# Encoder.net
KiCad netlist of a schematic drawn in EAGLE
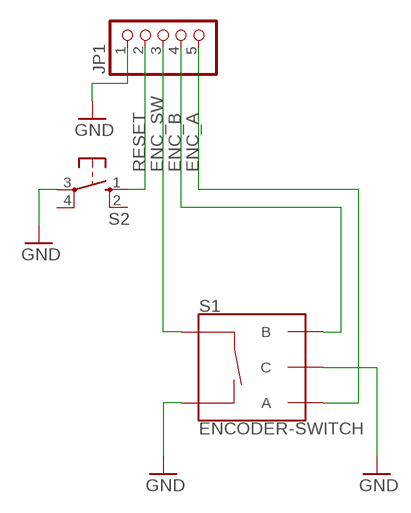
[diagram p0: schematic, sheet 1]

(export (version "E")
  (design (tool "Eeschema 10.0.6"))
  (components
    (comp (ref "JP1")
      (value "PINHD-1X5/90")
      (footprint "eagle-import:1X05_90")
      (libsource (lib "eagle-import") (part "PINHD-1X5/90"))
    )
    (comp (ref "S1")
      (value "ENCODER-SWITCH")
      (footprint "eagle-import:ROTARY_ENC_PLAIN")
      (libsource (lib "eagle-import") (part "ENCODER-SWITCH"))
    )
    (comp (ref "S2")
      (value "10-XX")
      (footprint "eagle-import:B3F-10XX")
      (fields (field (name "MPN") "B3F-1000"))
      (libsource (lib "eagle-import") (part "10-XX"))
    )
  )
  (nets
    (net (code "1") (name "/ENC_A") (class "Default")
      (node (ref "JP1") (pin "5") (pinfunction "5_5") (pintype "passive"))
      (node (ref "S1") (pin "A") (pinfunction "A_A") (pintype "bidirectional"))
    )
    (net (code "2") (name "/ENC_B") (class "Default")
      (node (ref "JP1") (pin "4") (pinfunction "4_4") (pintype "passive"))
      (node (ref "S1") (pin "B") (pinfunction "B_B") (pintype "bidirectional"))
    )
    (net (code "3") (name "/ENC_SW") (class "Default")
      (node (ref "JP1") (pin "3") (pinfunction "3_3") (pintype "passive"))
      (node (ref "S1") (pin "SW+") (pinfunction "SW+_SW+") (pintype "bidirectional"))
    )
    (net (code "4") (name "/RESET") (class "Default")
      (node (ref "JP1") (pin "2") (pinfunction "2_2") (pintype "passive"))
      (node (ref "S2") (pin "1") (pinfunction "S_1") (pintype "passive"))
    )
    (net (code "5") (name "GND") (class "Default")
      (node (ref "JP1") (pin "1") (pinfunction "1_1") (pintype "passive"))
      (node (ref "S1") (pin "C") (pinfunction "C_C") (pintype "bidirectional"))
      (node (ref "S1") (pin "SW-") (pinfunction "SW-_SW-") (pintype "bidirectional"))
      (node (ref "S2") (pin "3") (pinfunction "P_3") (pintype "passive"))
    )
    (net (code "6") (name "unconnected-(S2-P1-Pad4)") (class "Default")
      (node (ref "S2") (pin "4") (pinfunction "P1_4") (pintype "passive"))
    )
    (net (code "7") (name "unconnected-(S2-S1-Pad2)") (class "Default")
      (node (ref "S2") (pin "2") (pinfunction "S1_2") (pintype "passive"))
    )
  )
)
